# untitled.net
KiCad netlist of a schematic drawn in EAGLE
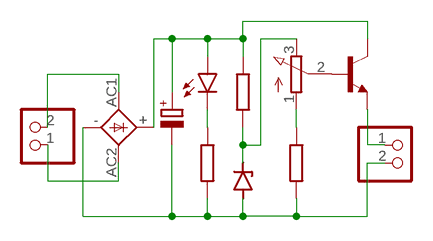
[diagram p0: schematic, sheet 1]

(export (version "E")
  (design (tool "Eeschema 10.0.6"))
  (components
    (comp (ref "1N47430_13V_1W")
      (value "1N4728")
      (footprint "eagle-import:DO41Z10")
      (libsource (lib "eagle-import") (part "1N4728"))
    )
    (comp (ref "B5K_1W")
      (value "B5K")
      (footprint "eagle-import:3RP_1610N")
      (libsource (lib "eagle-import") (part "3RP/1610N"))
    )
    (comp (ref "BD137_60V_1.5A")
      (value "BC547")
      (footprint "eagle-import:TO92")
      (libsource (lib "eagle-import") (part "BC547"))
    )
    (comp (ref "CR25_2000OHM")
      (value "2k")
      (footprint "eagle-import:0207_10")
      (libsource (lib "eagle-import") (part "R-EU_0207/10"))
    )
    (comp (ref "CR25_2700OHM")
      (value "2.7k")
      (footprint "eagle-import:0207_10")
      (libsource (lib "eagle-import") (part "R-EU_0207/10"))
    )
    (comp (ref "CR25_6800OHM")
      (value "6.8k")
      (footprint "eagle-import:0207_10")
      (libsource (lib "eagle-import") (part "R-EU_0207/10"))
    )
    (comp (ref "ELCO_680UF_25V")
      (value "680 uF")
      (footprint "eagle-import:E5-10,5")
      (libsource (lib "eagle-import") (part "CPOL-EUE5-10.5"))
    )
    (comp (ref "IN")
      (value "In")
      (footprint "eagle-import:1X02")
      (libsource (lib "eagle-import") (part "PINHD-1X2"))
    )
    (comp (ref "KBP206_2A_600V_TOWER")
      (value "2A 600V")
      (footprint "eagle-import:1KAB")
      (libsource (lib "eagle-import") (part "1KAB"))
    )
    (comp (ref "LED_VERMELHO")
      (value "LedR")
      (footprint "eagle-import:LED5MM")
      (libsource (lib "eagle-import") (part "LED5MM"))
    )
    (comp (ref "OUT")
      (value "Out")
      (footprint "eagle-import:1X02")
      (libsource (lib "eagle-import") (part "PINHD-1X2"))
    )
  )
  (nets
    (net (code "1") (name "Net-(1N47430_13V_1W-PadA)") (class "Default")
      (node (ref "1N47430_13V_1W") (pin "A") (pinfunction "A_A") (pintype "passive"))
      (node (ref "CR25_2000OHM") (pin "2") (pinfunction "2_2") (pintype "passive"))
      (node (ref "CR25_6800OHM") (pin "2") (pinfunction "2_2") (pintype "passive"))
      (node (ref "ELCO_680UF_25V") (pin "-") (pinfunction "-_-") (pintype "passive"))
      (node (ref "KBP206_2A_600V_TOWER") (pin "-") (pinfunction "-_-") (pintype "passive"))
      (node (ref "OUT") (pin "2") (pinfunction "2_2") (pintype "passive"))
    )
    (net (code "2") (name "Net-(B5K_1W-A)") (class "Default")
      (node (ref "B5K_1W") (pin "1") (pinfunction "A_1") (pintype "passive"))
      (node (ref "CR25_2000OHM") (pin "1") (pinfunction "1_1") (pintype "passive"))
    )
    (net (code "3") (name "Net-(B5K_1W-E)") (class "Default")
      (node (ref "1N47430_13V_1W") (pin "C") (pinfunction "C_C") (pintype "passive"))
      (node (ref "B5K_1W") (pin "3") (pinfunction "E_3") (pintype "passive"))
      (node (ref "CR25_2700OHM") (pin "2") (pinfunction "2_2") (pintype "passive"))
    )
    (net (code "4") (name "Net-(B5K_1W-S)") (class "Default")
      (node (ref "B5K_1W") (pin "2") (pinfunction "S_2") (pintype "passive"))
      (node (ref "BD137_60V_1.5A") (pin "2") (pinfunction "B_2") (pintype "passive"))
    )
    (net (code "5") (name "Net-(BD137_60V_1.5A-C)") (class "Default")
      (node (ref "BD137_60V_1.5A") (pin "3") (pinfunction "C_3") (pintype "passive"))
      (node (ref "CR25_2700OHM") (pin "1") (pinfunction "1_1") (pintype "passive"))
      (node (ref "ELCO_680UF_25V") (pin "+") (pinfunction "+_+") (pintype "passive"))
      (node (ref "KBP206_2A_600V_TOWER") (pin "+") (pinfunction "+_+") (pintype "passive"))
      (node (ref "LED_VERMELHO") (pin "A") (pinfunction "A_A") (pintype "passive"))
    )
    (net (code "6") (name "Net-(BD137_60V_1.5A-E)") (class "Default")
      (node (ref "BD137_60V_1.5A") (pin "1") (pinfunction "E_1") (pintype "passive"))
      (node (ref "OUT") (pin "1") (pinfunction "1_1") (pintype "passive"))
    )
    (net (code "7") (name "Net-(IN-Pad1)") (class "Default")
      (node (ref "IN") (pin "1") (pinfunction "1_1") (pintype "passive"))
      (node (ref "KBP206_2A_600V_TOWER") (pin "AC2") (pinfunction "AC2_AC2") (pintype "passive"))
    )
    (net (code "8") (name "Net-(IN-Pad2)") (class "Default")
      (node (ref "IN") (pin "2") (pinfunction "2_2") (pintype "passive"))
      (node (ref "KBP206_2A_600V_TOWER") (pin "AC1") (pinfunction "AC1_AC1") (pintype "passive"))
    )
    (net (code "9") (name "Net-(LED_VERMELHO-C)") (class "Default")
      (node (ref "CR25_6800OHM") (pin "1") (pinfunction "1_1") (pintype "passive"))
      (node (ref "LED_VERMELHO") (pin "K") (pinfunction "C_K") (pintype "passive"))
    )
  )
)
